# USB.net
KiCad netlist of a schematic drawn in Altium Designer
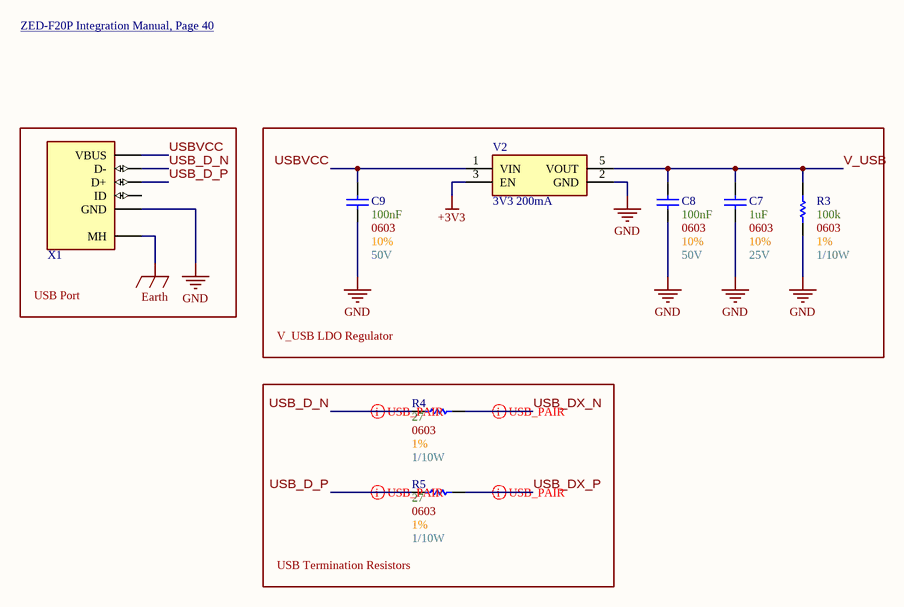
[diagram p0: USB.SchDoc]

(export (version "E")
  (design (tool "Eeschema 10.0.6"))
  (components
    (comp (ref "C7")
      (value "[Cap] 0603 1uF 10% 25V")
      (footprint "[Cap] SMD 0603")
      (description "CL10B105KA8NNNC")
      (fields
        (field (name "MAX VOLTAGE") "25V")
        (field (name "SIZE PACKAGE") "0603")
        (field (name "TOLERANCE") "10%")
        (field (name "CAPACITANCE") "1uF")
      )
      (libsource (lib "Capacitors") (part "[Cap] 0603 1uF 10% 25V"))
    )
    (comp (ref "C8")
      (value "[Cap] 0603 0.1uF 10% 50V")
      (footprint "[Cap] SMD 0603")
      (description "CL10B104KB8NNNC")
      (fields
        (field (name "MAX VOLTAGE") "50V")
        (field (name "SIZE PACKAGE") "0603")
        (field (name "TOLERANCE") "10%")
        (field (name "CAPACITANCE") "100nF")
      )
      (libsource (lib "Capacitors") (part "[Cap] 0603 0.1uF 10% 50V"))
    )
    (comp (ref "C9")
      (value "[Cap] 0603 0.1uF 10% 50V")
      (footprint "[Cap] SMD 0603")
      (description "CL10B104KB8NNNC")
      (fields
        (field (name "MAX VOLTAGE") "50V")
        (field (name "SIZE PACKAGE") "0603")
        (field (name "TOLERANCE") "10%")
        (field (name "CAPACITANCE") "100nF")
      )
      (libsource (lib "Capacitors") (part "[Cap] 0603 0.1uF 10% 50V"))
    )
    (comp (ref "R3")
      (value "[100k] SMD 0603 1% 1/10W")
      (footprint "[Res] SMD 0603")
      (description "RC0603FR-07100KL")
      (fields
        (field (name "WATTAGE") "1/10W")
        (field (name "TOLERANCE") "1%")
        (field (name "RESISTANCE") "100k")
        (field (name "SIZE PACKAGE") "0603")
      )
      (libsource (lib "Resistors") (part "[100k] SMD 0603 1% 1/10W"))
    )
    (comp (ref "R4")
      (value "[27] SMD 0603 1% 1/10W")
      (footprint "[Res] SMD 0603")
      (description "MCT06030C2709FP500")
      (fields
        (field (name "WATTAGE") "1/10W")
        (field (name "TOLERANCE") "1%")
        (field (name "RESISTANCE") "27")
        (field (name "SIZE PACKAGE") "0603")
      )
      (libsource (lib "Resistors") (part "[27] SMD 0603 1% 1/10W"))
    )
    (comp (ref "R5")
      (value "[27] SMD 0603 1% 1/10W")
      (footprint "[Res] SMD 0603")
      (description "MCT06030C2709FP500")
      (fields
        (field (name "WATTAGE") "1/10W")
        (field (name "TOLERANCE") "1%")
        (field (name "RESISTANCE") "27")
        (field (name "SIZE PACKAGE") "0603")
      )
      (libsource (lib "Resistors") (part "[27] SMD 0603 1% 1/10W"))
    )
    (comp (ref "V2")
      (value "3V3 200mA")
      (footprint "[Linear] 3V3 0.2A")
      (description "TCR2EF33,LM(CT")
      (libsource (lib "Voltage Regulators") (part "[Linear] 3V3 0.2A"))
    )
    (comp (ref "X1")
      (value "[USB] Type-B Mini")
      (footprint "[USB] Type-B Mini")
      (description "MUSB-05-S-B-SM-A-K-TR")
      (libsource (lib "Connectors") (part "[USB] Type-B Mini"))
    )
  )
  (nets
    (net (code "1") (name "+3V3") (class "Default")
      (node (ref "V2") (pin "3") (pinfunction "EN_3") (pintype "passive"))
    )
    (net (code "2") (name "/USBVCC") (class "Default")
      (node (ref "C9") (pin "2") (pinfunction "2_2") (pintype "passive"))
      (node (ref "V2") (pin "1") (pinfunction "VIN_1") (pintype "passive"))
      (node (ref "X1") (pin "1") (pinfunction "VBUS_1") (pintype "power_in"))
    )
    (net (code "3") (name "/USB_DX_N") (class "Default")
      (node (ref "R4") (pin "2") (pinfunction "2_2") (pintype "passive"))
    )
    (net (code "4") (name "/USB_DX_P") (class "Default")
      (node (ref "R5") (pin "2") (pinfunction "2_2") (pintype "passive"))
    )
    (net (code "5") (name "/USB_D_N") (class "Default")
      (node (ref "R4") (pin "1") (pinfunction "1_1") (pintype "passive"))
      (node (ref "X1") (pin "2") (pinfunction "D-_2") (pintype "bidirectional"))
    )
    (net (code "6") (name "/USB_D_P") (class "Default")
      (node (ref "R5") (pin "1") (pinfunction "1_1") (pintype "passive"))
      (node (ref "X1") (pin "3") (pinfunction "D+_3") (pintype "bidirectional"))
    )
    (net (code "7") (name "/V_USB") (class "Default")
      (node (ref "C7") (pin "2") (pinfunction "2_2") (pintype "passive"))
      (node (ref "C8") (pin "2") (pinfunction "2_2") (pintype "passive"))
      (node (ref "R3") (pin "2") (pinfunction "2_2") (pintype "passive"))
      (node (ref "V2") (pin "5") (pinfunction "VOUT_5") (pintype "passive"))
    )
    (net (code "8") (name "Earth") (class "Default")
      (node (ref "X1") (pin "MH") (pinfunction "MH_MH") (pintype "power_in"))
    )
    (net (code "9") (name "GND") (class "Default")
      (node (ref "C7") (pin "1") (pinfunction "1_1") (pintype "passive"))
      (node (ref "C8") (pin "1") (pinfunction "1_1") (pintype "passive"))
      (node (ref "C9") (pin "1") (pinfunction "1_1") (pintype "passive"))
      (node (ref "R3") (pin "1") (pinfunction "1_1") (pintype "passive"))
      (node (ref "V2") (pin "2") (pinfunction "GND_2") (pintype "passive"))
      (node (ref "X1") (pin "5") (pinfunction "GND_5") (pintype "power_in"))
    )
    (net (code "10") (name "unconnected-(X1-ID-Pad4)") (class "Default")
      (node (ref "X1") (pin "4") (pinfunction "ID_4") (pintype "bidirectional"))
    )
  )
)
